# ESP32.net
KiCad netlist of a schematic drawn in Altium Designer
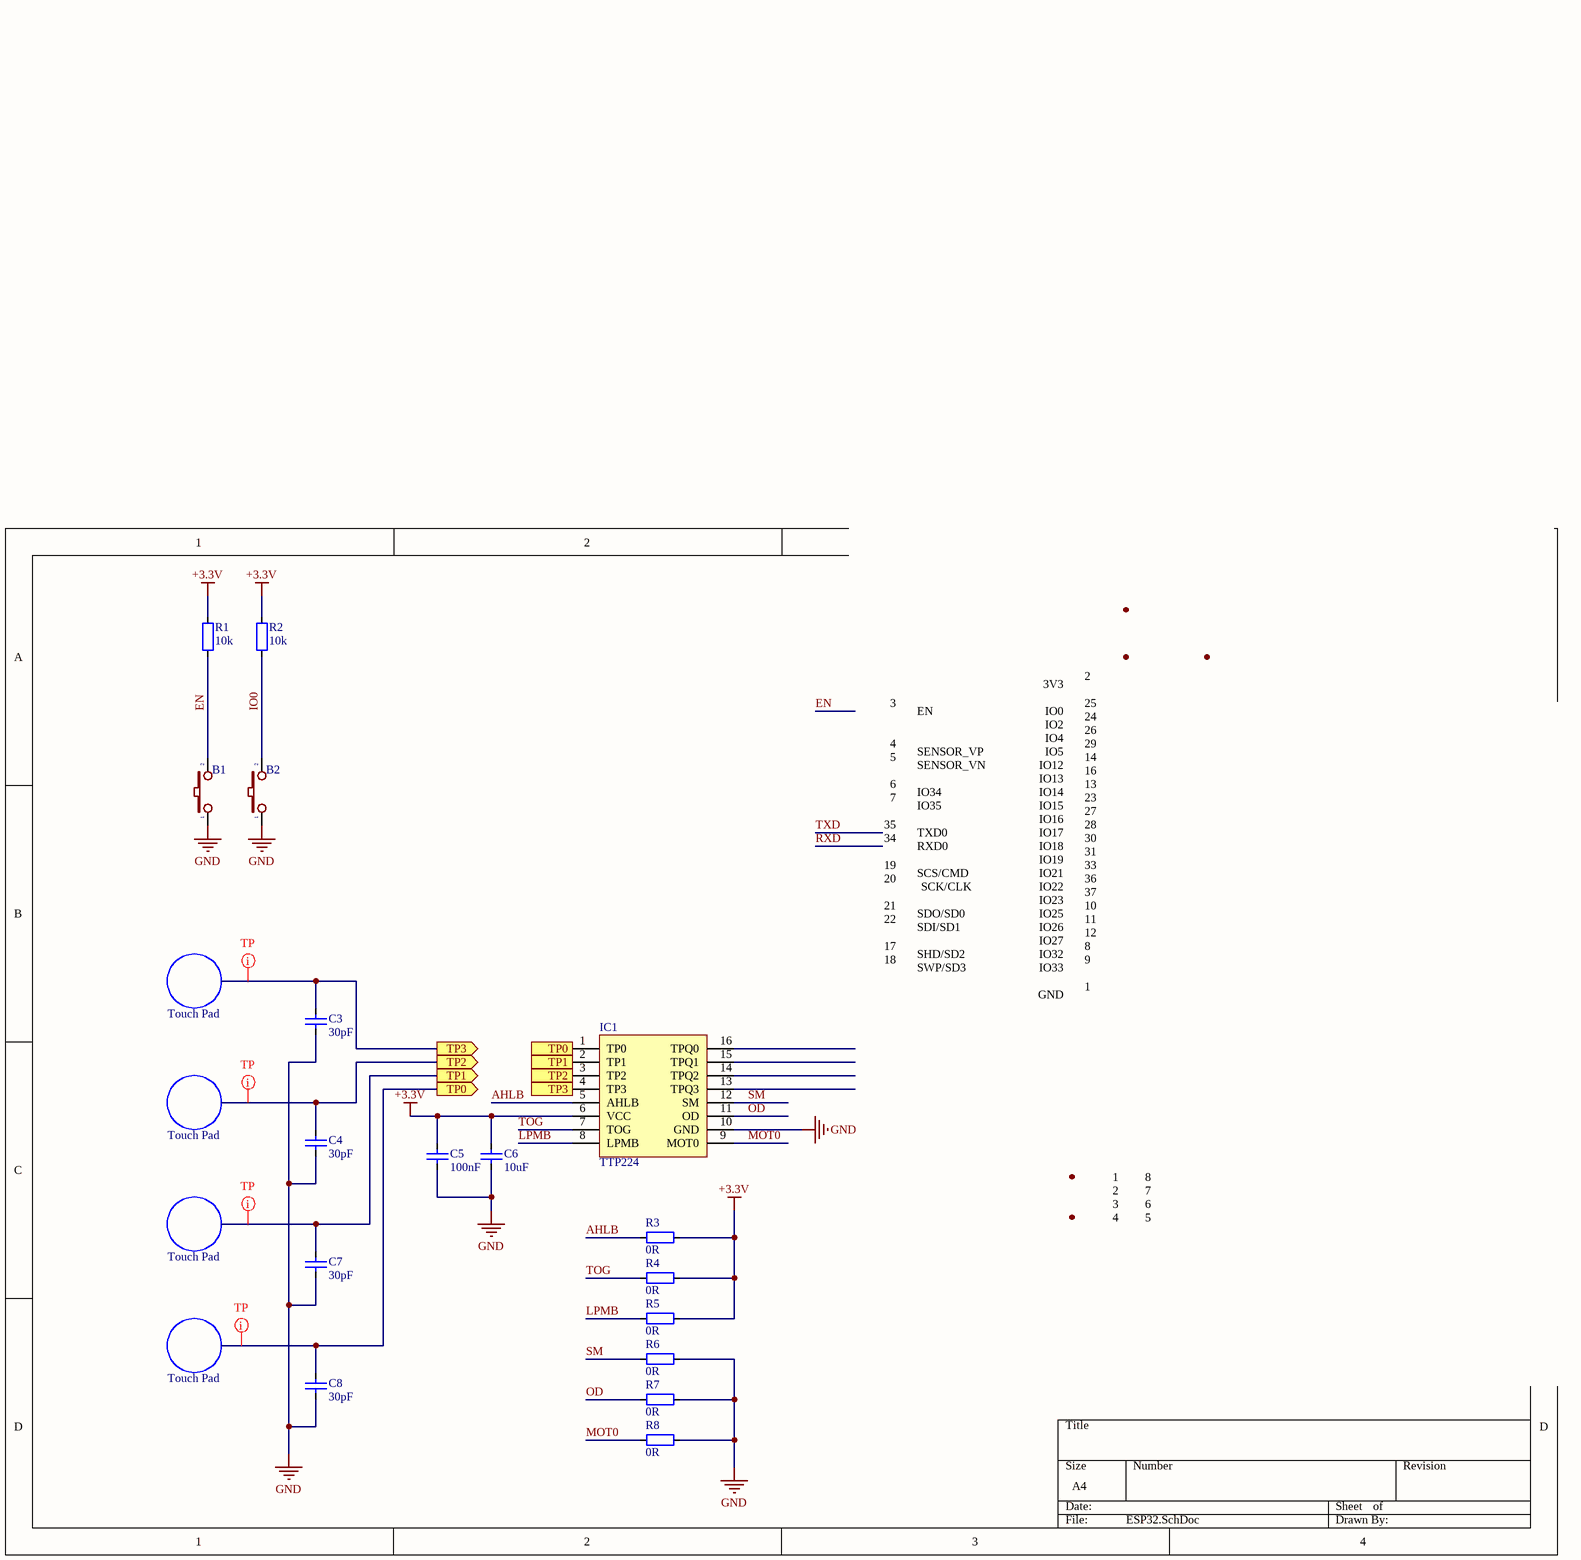
[diagram p0: ESP32.SchDoc]

(export (version "E")
  (design (tool "Eeschema 10.0.6"))
  (components
    (comp (ref "B1")
      (value "Button 3x4x2.5")
      (footprint "Button 3x4x2.5")
      (libsource (lib "My Library") (part "Button 3x4x2.5"))
    )
    (comp (ref "B2")
      (value "Button 3x4x2.5")
      (footprint "Button 3x4x2.5")
      (libsource (lib "My Library") (part "Button 3x4x2.5"))
    )
    (comp (ref "C1")
      (value "100nF")
      (footprint "CAP_0805")
      (description "Capacitor")
      (fields (field (name "PUBLISHER") "Altium Limited"))
      (libsource (lib "My Library") (part "CapSMD"))
    )
    (comp (ref "C2")
      (value "10uF")
      (footprint "CAP_0805")
      (description "Capacitor")
      (fields (field (name "PUBLISHER") "Altium Limited"))
      (libsource (lib "My Library") (part "CapSMD"))
    )
    (comp (ref "C3")
      (value "30pF")
      (footprint "CAP_0805")
      (description "Capacitor")
      (fields (field (name "PUBLISHER") "Altium Limited"))
      (libsource (lib "My Library") (part "CapSMD"))
    )
    (comp (ref "C4")
      (value "30pF")
      (footprint "CAP_0805")
      (description "Capacitor")
      (fields (field (name "PUBLISHER") "Altium Limited"))
      (libsource (lib "My Library") (part "CapSMD"))
    )
    (comp (ref "C5")
      (value "100nF")
      (footprint "CAP_0805")
      (description "Capacitor")
      (fields (field (name "PUBLISHER") "Altium Limited"))
      (libsource (lib "My Library") (part "CapSMD"))
    )
    (comp (ref "C6")
      (value "10uF")
      (footprint "CAP_0805")
      (description "Capacitor")
      (fields (field (name "PUBLISHER") "Altium Limited"))
      (libsource (lib "My Library") (part "CapSMD"))
    )
    (comp (ref "C7")
      (value "30pF")
      (footprint "CAP_0805")
      (description "Capacitor")
      (fields (field (name "PUBLISHER") "Altium Limited"))
      (libsource (lib "My Library") (part "CapSMD"))
    )
    (comp (ref "C8")
      (value "30pF")
      (footprint "CAP_0805")
      (description "Capacitor")
      (fields (field (name "PUBLISHER") "Altium Limited"))
      (libsource (lib "My Library") (part "CapSMD"))
    )
    (comp (ref "IC1") (value "TTP224") (footprint "TTP224") (libsource (lib "My Library") (part "TTP224")))
    (comp (ref "JP1")
      (value "JP 2x4 2.54")
      (footprint "JP2x4_PAD")
      (description "Cắm")
      (libsource (lib "Altium_Lib_by_KhueNguyenCreator") (part "JP 2x4 2.54 Duc Thang"))
    )
    (comp (ref "R1")
      (value "10k")
      (footprint "RES-SMD-0603")
      (description "Resistor")
      (fields
        (field (name "MANUFACTURER") "Generic Components")
        (field (name "PUBLISHER") "Altium Hobart Technology Centre")
      )
      (libsource (lib "My Library") (part "Resistor - SMD"))
    )
    (comp (ref "R2")
      (value "10k")
      (footprint "RES-SMD-0603")
      (description "Resistor")
      (fields
        (field (name "MANUFACTURER") "Generic Components")
        (field (name "PUBLISHER") "Altium Hobart Technology Centre")
      )
      (libsource (lib "My Library") (part "Resistor - SMD"))
    )
    (comp (ref "R3")
      (value "0R")
      (footprint "RES-SMD-0603")
      (description "Resistor")
      (fields
        (field (name "MANUFACTURER") "Generic Components")
        (field (name "PUBLISHER") "Altium Hobart Technology Centre")
      )
      (libsource (lib "My Library") (part "Resistor - SMD"))
    )
    (comp (ref "R4")
      (value "0R")
      (footprint "RES-SMD-0603")
      (description "Resistor")
      (fields
        (field (name "MANUFACTURER") "Generic Components")
        (field (name "PUBLISHER") "Altium Hobart Technology Centre")
      )
      (libsource (lib "My Library") (part "Resistor - SMD"))
    )
    (comp (ref "R5")
      (value "0R")
      (footprint "RES-SMD-0603")
      (description "Resistor")
      (fields
        (field (name "MANUFACTURER") "Generic Components")
        (field (name "PUBLISHER") "Altium Hobart Technology Centre")
      )
      (libsource (lib "My Library") (part "Resistor - SMD"))
    )
    (comp (ref "R6")
      (value "0R")
      (footprint "RES-SMD-0603")
      (description "Resistor")
      (fields
        (field (name "MANUFACTURER") "Generic Components")
        (field (name "PUBLISHER") "Altium Hobart Technology Centre")
      )
      (libsource (lib "My Library") (part "Resistor - SMD"))
    )
    (comp (ref "R7")
      (value "0R")
      (footprint "RES-SMD-0603")
      (description "Resistor")
      (fields
        (field (name "MANUFACTURER") "Generic Components")
        (field (name "PUBLISHER") "Altium Hobart Technology Centre")
      )
      (libsource (lib "My Library") (part "Resistor - SMD"))
    )
    (comp (ref "R8")
      (value "0R")
      (footprint "RES-SMD-0603")
      (description "Resistor")
      (fields
        (field (name "MANUFACTURER") "Generic Components")
        (field (name "PUBLISHER") "Altium Hobart Technology Centre")
      )
      (libsource (lib "My Library") (part "Resistor - SMD"))
    )
    (comp (ref "U1")
      (value "ESP32-WROOM-32")
      (footprint "MODULE_ESP32-WROOM-32")
      (description "Bluetooth, WiFi Transceiver Module 2.4GHz ~ 2.5GHz Surface Mount")
      (fields (field (name "MF") "Espressif Systems") (field (name "DIGI-KEY_PART_NUMBER") "1904-1010-1-ND"))
      (libsource (lib "My Library") (part "ESP32-WROOM-32"))
    )
  )
  (nets
    (net (code "1") (name "+3.3V") (class "Default")
      (node (ref "C1") (pin "1") (pinfunction "1_1") (pintype "passive"))
      (node (ref "C2") (pin "1") (pinfunction "1_1") (pintype "passive"))
      (node (ref "C5") (pin "2") (pinfunction "2_2") (pintype "passive"))
      (node (ref "C6") (pin "2") (pinfunction "2_2") (pintype "passive"))
      (node (ref "IC1") (pin "6") (pinfunction "VCC_6") (pintype "passive"))
      (node (ref "R1") (pin "1") (pinfunction "1_1") (pintype "passive"))
      (node (ref "R2") (pin "1") (pinfunction "1_1") (pintype "passive"))
      (node (ref "R3") (pin "2") (pinfunction "2_2") (pintype "passive"))
      (node (ref "R4") (pin "2") (pinfunction "2_2") (pintype "passive"))
      (node (ref "R5") (pin "2") (pinfunction "2_2") (pintype "passive"))
      (node (ref "U1") (pin "2") (pinfunction "3V3_2") (pintype "power_in"))
    )
    (net (code "2") (name "+12") (class "Default")
      (node (ref "JP1") (pin "1") (pinfunction "1_1") (pintype "passive"))
      (node (ref "JP1") (pin "2") (pinfunction "2_2") (pintype "passive"))
    )
    (net (code "3") (name "/AHLB") (class "Default")
      (node (ref "IC1") (pin "5") (pinfunction "AHLB_5") (pintype "passive"))
      (node (ref "R3") (pin "1") (pinfunction "1_1") (pintype "passive"))
    )
    (net (code "4") (name "/EN") (class "Default")
      (node (ref "B1") (pin "2") (pinfunction "2_2") (pintype "passive"))
      (node (ref "R1") (pin "2") (pinfunction "2_2") (pintype "passive"))
      (node (ref "U1") (pin "3") (pinfunction "EN_3") (pintype "input"))
    )
    (net (code "5") (name "/IO0") (class "Default")
      (node (ref "B2") (pin "2") (pinfunction "2_2") (pintype "passive"))
      (node (ref "R2") (pin "2") (pinfunction "2_2") (pintype "passive"))
      (node (ref "U1") (pin "25") (pinfunction "IO0_25") (pintype "bidirectional"))
    )
    (net (code "6") (name "/IO4") (class "Default")
      (node (ref "IC1") (pin "16") (pinfunction "TPQ0_16") (pintype "passive"))
      (node (ref "U1") (pin "26") (pinfunction "IO4_26") (pintype "bidirectional"))
    )
    (net (code "7") (name "/IO13") (class "Default")
      (node (ref "U1") (pin "16") (pinfunction "IO13_16") (pintype "bidirectional"))
    )
    (net (code "8") (name "/IO16") (class "Default")
      (node (ref "JP1") (pin "5") (pinfunction "5_5") (pintype "passive"))
      (node (ref "U1") (pin "27") (pinfunction "IO16_27") (pintype "bidirectional"))
    )
    (net (code "9") (name "/IO17") (class "Default")
      (node (ref "JP1") (pin "6") (pinfunction "6_6") (pintype "passive"))
      (node (ref "U1") (pin "28") (pinfunction "IO17_28") (pintype "bidirectional"))
    )
    (net (code "10") (name "/IO18") (class "Default")
      (node (ref "JP1") (pin "7") (pinfunction "7_7") (pintype "passive"))
      (node (ref "U1") (pin "30") (pinfunction "IO18_30") (pintype "bidirectional"))
    )
    (net (code "11") (name "/IO19") (class "Default")
      (node (ref "JP1") (pin "8") (pinfunction "8_8") (pintype "passive"))
      (node (ref "U1") (pin "31") (pinfunction "IO19_31") (pintype "bidirectional"))
    )
    (net (code "12") (name "/IO21") (class "Default")
      (node (ref "IC1") (pin "15") (pinfunction "TPQ1_15") (pintype "passive"))
      (node (ref "U1") (pin "33") (pinfunction "IO21_33") (pintype "bidirectional"))
    )
    (net (code "13") (name "/IO22") (class "Default")
      (node (ref "IC1") (pin "14") (pinfunction "TPQ2_14") (pintype "passive"))
      (node (ref "U1") (pin "36") (pinfunction "IO22_36") (pintype "bidirectional"))
    )
    (net (code "14") (name "/IO23") (class "Default")
      (node (ref "IC1") (pin "13") (pinfunction "TPQ3_13") (pintype "passive"))
      (node (ref "U1") (pin "37") (pinfunction "IO23_37") (pintype "bidirectional"))
    )
    (net (code "15") (name "/IO25") (class "Default")
      (node (ref "U1") (pin "10") (pinfunction "IO25_10") (pintype "bidirectional"))
    )
    (net (code "16") (name "/IO33") (class "Default")
      (node (ref "U1") (pin "9") (pinfunction "IO33_9") (pintype "bidirectional"))
    )
    (net (code "17") (name "/LPMB") (class "Default")
      (node (ref "IC1") (pin "8") (pinfunction "LPMB_8") (pintype "passive"))
      (node (ref "R5") (pin "1") (pinfunction "1_1") (pintype "passive"))
    )
    (net (code "18") (name "/MOT0") (class "Default")
      (node (ref "IC1") (pin "9") (pinfunction "MOT0_9") (pintype "passive"))
      (node (ref "R8") (pin "1") (pinfunction "1_1") (pintype "passive"))
    )
    (net (code "19") (name "/OD") (class "Default")
      (node (ref "IC1") (pin "11") (pinfunction "OD_11") (pintype "passive"))
      (node (ref "R7") (pin "1") (pinfunction "1_1") (pintype "passive"))
    )
    (net (code "20") (name "/RXD") (class "Default")
      (node (ref "U1") (pin "34") (pinfunction "RXD0_34") (pintype "bidirectional"))
    )
    (net (code "21") (name "/SM") (class "Default")
      (node (ref "IC1") (pin "12") (pinfunction "SM_12") (pintype "passive"))
      (node (ref "R6") (pin "1") (pinfunction "1_1") (pintype "passive"))
    )
    (net (code "22") (name "/TOG") (class "Default")
      (node (ref "IC1") (pin "7") (pinfunction "TOG_7") (pintype "passive"))
      (node (ref "R4") (pin "1") (pinfunction "1_1") (pintype "passive"))
    )
    (net (code "23") (name "/TP0") (class "Default")
      (node (ref "C8") (pin "2") (pinfunction "2_2") (pintype "passive"))
      (node (ref "IC1") (pin "1") (pinfunction "TP0_1") (pintype "passive"))
    )
    (net (code "24") (name "/TP1") (class "Default")
      (node (ref "C7") (pin "2") (pinfunction "2_2") (pintype "passive"))
      (node (ref "IC1") (pin "2") (pinfunction "TP1_2") (pintype "passive"))
    )
    (net (code "25") (name "/TP2") (class "Default")
      (node (ref "C4") (pin "2") (pinfunction "2_2") (pintype "passive"))
      (node (ref "IC1") (pin "3") (pinfunction "TP2_3") (pintype "passive"))
    )
    (net (code "26") (name "/TP3") (class "Default")
      (node (ref "C3") (pin "2") (pinfunction "2_2") (pintype "passive"))
      (node (ref "IC1") (pin "4") (pinfunction "TP3_4") (pintype "passive"))
    )
    (net (code "27") (name "/TXD") (class "Default")
      (node (ref "U1") (pin "35") (pinfunction "TXD0_35") (pintype "bidirectional"))
    )
    (net (code "28") (name "GND") (class "Default")
      (node (ref "B1") (pin "1") (pinfunction "1_1") (pintype "passive"))
      (node (ref "B2") (pin "1") (pinfunction "1_1") (pintype "passive"))
      (node (ref "C1") (pin "2") (pinfunction "2_2") (pintype "passive"))
      (node (ref "C2") (pin "2") (pinfunction "2_2") (pintype "passive"))
      (node (ref "C3") (pin "1") (pinfunction "1_1") (pintype "passive"))
      (node (ref "C4") (pin "1") (pinfunction "1_1") (pintype "passive"))
      (node (ref "C5") (pin "1") (pinfunction "1_1") (pintype "passive"))
      (node (ref "C6") (pin "1") (pinfunction "1_1") (pintype "passive"))
      (node (ref "C7") (pin "1") (pinfunction "1_1") (pintype "passive"))
      (node (ref "C8") (pin "1") (pinfunction "1_1") (pintype "passive"))
      (node (ref "IC1") (pin "10") (pinfunction "GND_10") (pintype "passive"))
      (node (ref "JP1") (pin "3") (pinfunction "3_3") (pintype "passive"))
      (node (ref "JP1") (pin "4") (pinfunction "4_4") (pintype "passive"))
      (node (ref "R6") (pin "2") (pinfunction "2_2") (pintype "passive"))
      (node (ref "R7") (pin "2") (pinfunction "2_2") (pintype "passive"))
      (node (ref "R8") (pin "2") (pinfunction "2_2") (pintype "passive"))
      (node (ref "U1") (pin "1") (pinfunction "GND_1") (pintype "power_in"))
    )
    (net (code "29") (name "unconnected-(U1-IO2-Pad24)") (class "Default")
      (node (ref "U1") (pin "24") (pinfunction "IO2_24") (pintype "bidirectional"))
    )
    (net (code "30") (name "unconnected-(U1-IO5-Pad29)") (class "Default")
      (node (ref "U1") (pin "29") (pinfunction "IO5_29") (pintype "bidirectional"))
    )
    (net (code "31") (name "unconnected-(U1-IO12-Pad14)") (class "Default")
      (node (ref "U1") (pin "14") (pinfunction "IO12_14") (pintype "bidirectional"))
    )
    (net (code "32") (name "unconnected-(U1-IO14-Pad13)") (class "Default")
      (node (ref "U1") (pin "13") (pinfunction "IO14_13") (pintype "bidirectional"))
    )
    (net (code "33") (name "unconnected-(U1-IO15-Pad23)") (class "Default")
      (node (ref "U1") (pin "23") (pinfunction "IO15_23") (pintype "bidirectional"))
    )
    (net (code "34") (name "unconnected-(U1-IO26-Pad11)") (class "Default")
      (node (ref "U1") (pin "11") (pinfunction "IO26_11") (pintype "bidirectional"))
    )
    (net (code "35") (name "unconnected-(U1-IO27-Pad12)") (class "Default")
      (node (ref "U1") (pin "12") (pinfunction "IO27_12") (pintype "bidirectional"))
    )
    (net (code "36") (name "unconnected-(U1-IO32-Pad8)") (class "Default")
      (node (ref "U1") (pin "8") (pinfunction "IO32_8") (pintype "bidirectional"))
    )
    (net (code "37") (name "unconnected-(U1-IO34-Pad6)") (class "Default")
      (node (ref "U1") (pin "6") (pinfunction "IO34_6") (pintype "input"))
    )
    (net (code "38") (name "unconnected-(U1-IO35-Pad7)") (class "Default")
      (node (ref "U1") (pin "7") (pinfunction "IO35_7") (pintype "input"))
    )
    (net (code "39") (name "unconnected-(U1-SCK{slash}CLK-Pad20)") (class "Default")
      (node (ref "U1") (pin "20") (pinfunction "SCK/CLK_20") (pintype "bidirectional"))
    )
    (net (code "40") (name "unconnected-(U1-SCS{slash}CMD-Pad19)") (class "Default")
      (node (ref "U1") (pin "19") (pinfunction "SCS/CMD_19") (pintype "bidirectional"))
    )
    (net (code "41") (name "unconnected-(U1-SDI{slash}SD1-Pad22)") (class "Default")
      (node (ref "U1") (pin "22") (pinfunction "SDI/SD1_22") (pintype "bidirectional"))
    )
    (net (code "42") (name "unconnected-(U1-SDO{slash}SD0-Pad21)") (class "Default")
      (node (ref "U1") (pin "21") (pinfunction "SDO/SD0_21") (pintype "bidirectional"))
    )
    (net (code "43") (name "unconnected-(U1-SENSOR_VN-Pad5)") (class "Default")
      (node (ref "U1") (pin "5") (pinfunction "SENSOR_VN_5") (pintype "input"))
    )
    (net (code "44") (name "unconnected-(U1-SENSOR_VP-Pad4)") (class "Default")
      (node (ref "U1") (pin "4") (pinfunction "SENSOR_VP_4") (pintype "input"))
    )
    (net (code "45") (name "unconnected-(U1-SHD{slash}SD2-Pad17)") (class "Default")
      (node (ref "U1") (pin "17") (pinfunction "SHD/SD2_17") (pintype "bidirectional"))
    )
    (net (code "46") (name "unconnected-(U1-SWP{slash}SD3-Pad18)") (class "Default")
      (node (ref "U1") (pin "18") (pinfunction "SWP/SD3_18") (pintype "bidirectional"))
    )
  )
)
